# mcu.net
KiCad netlist of a schematic drawn in Altium Designer
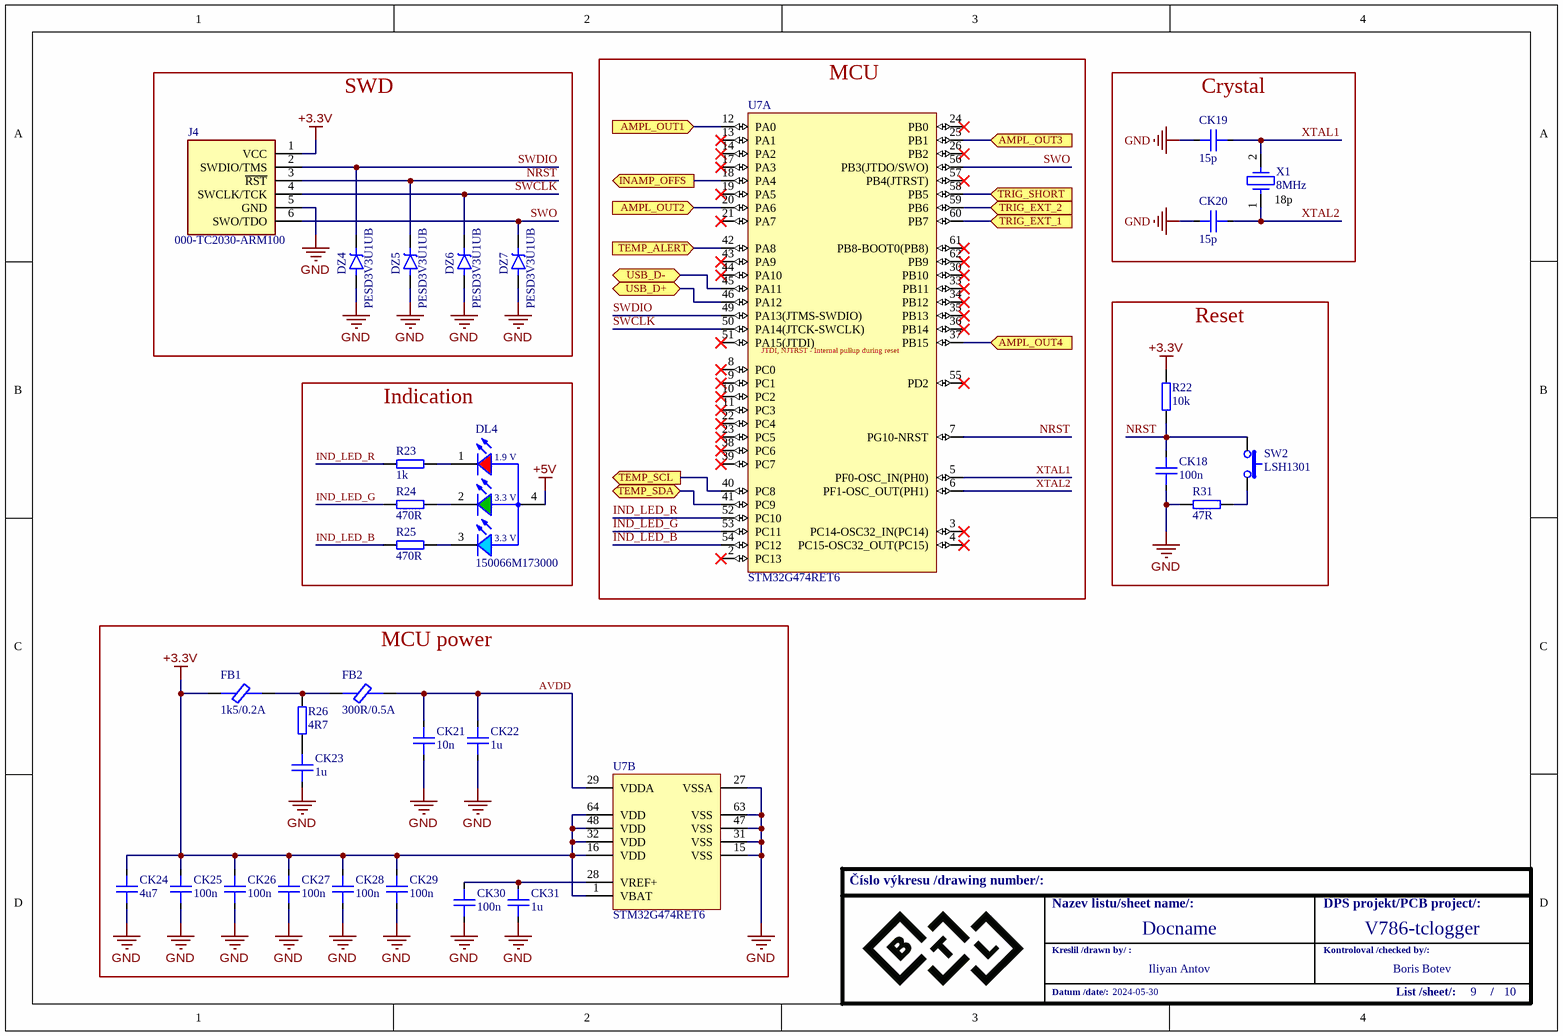
[diagram p0: mcu.SchDoc]

(export (version "E")
  (design (tool "Eeschema 10.0.6"))
  (components
    (comp (ref "CK18")
      (value "100n")
      (footprint "CAPC1608X09N(SMC0603)")
      (description "C; 100n; 100V; 10%; X7R; ??;")
      (fields
        (field (name "MANUFACTURER") "Murata Electronics: GRM188R72A104KA35D;;Yageo: CC0603KRX7R0BB104")
      )
      (libsource (lib "altium_sql") (part "CK"))
    )
    (comp (ref "CK19")
      (value "15p")
      (footprint "CAPC1608X09N(SMC0603)")
      (description "C; 15p; 25V; 5%; NP0/C0G; ??;")
      (fields (field (name "MANUFACTURER") "Samsung: CL10C150JB81PNC"))
      (libsource (lib "altium_sql") (part "CK"))
    )
    (comp (ref "CK20")
      (value "15p")
      (footprint "CAPC1608X09N(SMC0603)")
      (description "C; 15p; 25V; 5%; NP0/C0G; ??;")
      (fields (field (name "MANUFACTURER") "Samsung: CL10C150JB81PNC"))
      (libsource (lib "altium_sql") (part "CK"))
    )
    (comp (ref "CK21")
      (value "10n")
      (footprint "CAPC1608X09N(SMC0603)")
      (description "C; 10n; 50V; 5%; NP0/C0G; ??;")
      (fields (field (name "MANUFACTURER") "TDK: C1608C0G1H103J080AA"))
      (libsource (lib "altium_sql") (part "CK"))
    )
    (comp (ref "CK22")
      (value "1u")
      (footprint "CAPC1608X09N(SMC0603)")
      (description "C; 1u; 50V; 10%; X5R; ??;")
      (libsource (lib "altium_sql") (part "CK"))
    )
    (comp (ref "CK23")
      (value "1u")
      (footprint "CAPC1608X09N(SMC0603)")
      (description "C; 1u; 50V; 10%; X5R; ??;")
      (libsource (lib "altium_sql") (part "CK"))
    )
    (comp (ref "CK24")
      (value "4u7")
      (footprint "CAPC1608X09N(SMC0603)")
      (description "C; 4u7; 25V; 20%; X5R; ??;")
      (fields (field (name "MANUFACTURER") "TDK Corporation: C1608X5R1E475M080AC"))
      (libsource (lib "altium_sql") (part "CK"))
    )
    (comp (ref "CK25")
      (value "100n")
      (footprint "CAPC1608X09N(SMC0603)")
      (description "C; 100n; 100V; 10%; X7R; ??;")
      (fields
        (field (name "MANUFACTURER") "Murata Electronics: GRM188R72A104KA35D;;Yageo: CC0603KRX7R0BB104")
      )
      (libsource (lib "altium_sql") (part "CK"))
    )
    (comp (ref "CK26")
      (value "100n")
      (footprint "CAPC1608X09N(SMC0603)")
      (description "C; 100n; 100V; 10%; X7R; ??;")
      (fields
        (field (name "MANUFACTURER") "Murata Electronics: GRM188R72A104KA35D;;Yageo: CC0603KRX7R0BB104")
      )
      (libsource (lib "altium_sql") (part "CK"))
    )
    (comp (ref "CK27")
      (value "100n")
      (footprint "CAPC1608X09N(SMC0603)")
      (description "C; 100n; 100V; 10%; X7R; ??;")
      (fields
        (field (name "MANUFACTURER") "Murata Electronics: GRM188R72A104KA35D;;Yageo: CC0603KRX7R0BB104")
      )
      (libsource (lib "altium_sql") (part "CK"))
    )
    (comp (ref "CK28")
      (value "100n")
      (footprint "CAPC1608X09N(SMC0603)")
      (description "C; 100n; 100V; 10%; X7R; ??;")
      (fields
        (field (name "MANUFACTURER") "Murata Electronics: GRM188R72A104KA35D;;Yageo: CC0603KRX7R0BB104")
      )
      (libsource (lib "altium_sql") (part "CK"))
    )
    (comp (ref "CK29")
      (value "100n")
      (footprint "CAPC1608X09N(SMC0603)")
      (description "C; 100n; 100V; 10%; X7R; ??;")
      (fields
        (field (name "MANUFACTURER") "Murata Electronics: GRM188R72A104KA35D;;Yageo: CC0603KRX7R0BB104")
      )
      (libsource (lib "altium_sql") (part "CK"))
    )
    (comp (ref "CK30")
      (value "100n")
      (footprint "CAPC1608X09N(SMC0603)")
      (description "C; 100n; 100V; 10%; X7R; ??;")
      (fields
        (field (name "MANUFACTURER") "Murata Electronics: GRM188R72A104KA35D;;Yageo: CC0603KRX7R0BB104")
      )
      (libsource (lib "altium_sql") (part "CK"))
    )
    (comp (ref "CK31")
      (value "1u")
      (footprint "CAPC1608X09N(SMC0603)")
      (description "C; 1u; 50V; 10%; X5R; ??;")
      (libsource (lib "altium_sql") (part "CK"))
    )
    (comp (ref "DL4")
      (value "150066M173000")
      (footprint "WE_150066M173000")
      (description "Ind; Light; Red/Green/Blue;")
      (fields (field (name "MANUFACTURER") "Würth: 150066M173000"))
      (libsource (lib "altium_sql") (part "EDL+150066M173000X00"))
    )
    (comp (ref "DZ4")
      (value "PESD3V3U1UB")
      (footprint "SODFL160X65-2N(SC79)")
      (description "CP; Voltage [V] - Unidirectional; 4.5; R:Yes; 1x;")
      (fields (field (name "MANUFACTURER") "Nexperia: PESD3V3U1UB,115;;NXP: PESD3V3U1UB,115"))
      (libsource (lib "altium_sql") (part "DTU"))
    )
    (comp (ref "DZ5")
      (value "PESD3V3U1UB")
      (footprint "SODFL160X65-2N(SC79)")
      (description "CP; Voltage [V] - Unidirectional; 4.5; R:Yes; 1x;")
      (fields (field (name "MANUFACTURER") "Nexperia: PESD3V3U1UB,115;;NXP: PESD3V3U1UB,115"))
      (libsource (lib "altium_sql") (part "DTU"))
    )
    (comp (ref "DZ6")
      (value "PESD3V3U1UB")
      (footprint "SODFL160X65-2N(SC79)")
      (description "CP; Voltage [V] - Unidirectional; 4.5; R:Yes; 1x;")
      (fields (field (name "MANUFACTURER") "Nexperia: PESD3V3U1UB,115;;NXP: PESD3V3U1UB,115"))
      (libsource (lib "altium_sql") (part "DTU"))
    )
    (comp (ref "DZ7")
      (value "PESD3V3U1UB")
      (footprint "SODFL160X65-2N(SC79)")
      (description "CP; Voltage [V] - Unidirectional; 4.5; R:Yes; 1x;")
      (fields (field (name "MANUFACTURER") "Nexperia: PESD3V3U1UB,115;;NXP: PESD3V3U1UB,115"))
      (libsource (lib "altium_sql") (part "DTU"))
    )
    (comp (ref "FB1")
      (value "1k5/0.2A")
      (footprint "INDC2012X08N(SML0805)")
      (description "Flt; Chip Bead; 0.7Ohm; 0.2A; ??V; 1x;")
      (libsource (lib "altium_sql") (part "L_FB"))
    )
    (comp (ref "FB2")
      (value "300R/0.5A")
      (footprint "MMZ1608")
      (description "Flt; Chip Bead; 0.25Ohm; 0.5A; ??V; 1x;")
      (fields (field (name "MANUFACTURER") "TDK: MMZ1608B301CTAH0;;TDK: MMZ1608B301CT"))
      (libsource (lib "altium_sql") (part "L_FB"))
    )
    (comp (ref "J4")
      (value "000-TC2030-ARM100")
      (footprint "TC2030-MCP-NL")
      (description "De; Programming connector;")
      (libsource (lib "altium_sql") (part "000-TC2030-ARM100"))
    )
    (comp (ref "R22")
      (value "10k")
      (footprint "RESC2012X06N(SMR0805)")
      (description "R; 10k; 0.125W; 1%; 150V; Thick Film; ±100ppm/K; 1x;")
      (libsource (lib "altium_sql") (part "R"))
    )
    (comp (ref "R23")
      (value "1k")
      (footprint "RESC2012X06N(SMR0805)")
      (description "R; 1k; 0.125W; 1%; 150V; Thick Film; ±100ppm/K; 1x;")
      (libsource (lib "altium_sql") (part "R"))
    )
    (comp (ref "R24")
      (value "470R")
      (footprint "RESC1608X06N(SMR0603)")
      (description "R; 470R; 0.1W; 1%; 75V; Thick Film; ±100ppm/K; 1x;")
      (fields (field (name "MANUFACTURER") "Yageo: RC0603FR-07470RL;;Panasonic: ERJ3EKF4700V"))
      (libsource (lib "altium_sql") (part "R"))
    )
    (comp (ref "R25")
      (value "470R")
      (footprint "RESC1608X06N(SMR0603)")
      (description "R; 470R; 0.1W; 1%; 75V; Thick Film; ±100ppm/K; 1x;")
      (fields (field (name "MANUFACTURER") "Yageo: RC0603FR-07470RL;;Panasonic: ERJ3EKF4700V"))
      (libsource (lib "altium_sql") (part "R"))
    )
    (comp (ref "R26")
      (value "4R7")
      (footprint "RESC2012X06N(SMR0805)")
      (description "R; 4R7; 0.125W; 5%; 150V; Thick Film; ±200ppm/K; 1x;")
      (fields (field (name "MANUFACTURER") "YAGEO: RC0805FR-074R7L;;BC Components: MCU0805-50 1% P5 4R7"))
      (libsource (lib "altium_sql") (part "R"))
    )
    (comp (ref "R31")
      (value "47R")
      (footprint "RESC2012X06N(SMR0805)")
      (description "R; 47R; 0.125W; 1%; 150V; Thick Film; ±100ppm/K; 1x;")
      (libsource (lib "altium_sql") (part "R"))
    )
    (comp (ref "SW2")
      (value "LSH1301")
      (footprint "LSH_SWITCH")
      (description "MSw; SPST; PCB; 1x; DC:12V; DC:0.05A; AC:??V; AC:??A; CV:??V; Push-button;")
      (fields (field (name "MANUFACTURER") "DIPTRONICS: DTSM-62N-V-T/R"))
      (libsource (lib "altium_sql") (part "ESW+LSH1301XX0"))
    )
    (comp (ref "U7")
      (value "STM32G474RET6")
      (footprint "TSQFP50P1200X1200X160-64M")
      (libsource (lib "custom-footprints") (part "STM32G474RET6"))
    )
    (comp (ref "X1")
      (value "8MHz")
      (footprint "TXC_7A")
      (description "Oth; Crystal;")
      (fields (field (name "MANUFACTURER") "Abracon: ABM3-8.000MHZ-D2Y-T"))
      (libsource (lib "altium_sql") (part "XTAL_2PIN_1"))
    )
  )
  (nets
    (net (code "1") (name "+3.3V") (class "Default")
      (node (ref "CK24") (pin "2") (pinfunction "2_2") (pintype "passive"))
      (node (ref "CK25") (pin "2") (pinfunction "2_2") (pintype "passive"))
      (node (ref "CK26") (pin "2") (pinfunction "2_2") (pintype "passive"))
      (node (ref "CK27") (pin "2") (pinfunction "2_2") (pintype "passive"))
      (node (ref "CK28") (pin "2") (pinfunction "2_2") (pintype "passive"))
      (node (ref "CK29") (pin "2") (pinfunction "2_2") (pintype "passive"))
      (node (ref "FB1") (pin "1") (pinfunction "L1A_1") (pintype "passive"))
      (node (ref "J4") (pin "1") (pinfunction "VCC_1") (pintype "power_in"))
      (node (ref "R22") (pin "2") (pinfunction "2_2") (pintype "passive"))
      (node (ref "U7") (pin "1") (pinfunction "VBAT_1") (pintype "power_in"))
      (node (ref "U7") (pin "16") (pinfunction "VDD_16") (pintype "power_in"))
      (node (ref "U7") (pin "32") (pinfunction "VDD_32") (pintype "power_in"))
      (node (ref "U7") (pin "48") (pinfunction "VDD_48") (pintype "power_in"))
      (node (ref "U7") (pin "64") (pinfunction "VDD_64") (pintype "power_in"))
    )
    (net (code "2") (name "+5V") (class "Default")
      (node (ref "DL4") (pin "4") (pinfunction "A_4") (pintype "passive"))
    )
    (net (code "3") (name "/AMPL_OUT1") (class "Default")
      (node (ref "U7") (pin "12") (pinfunction "PA0_12") (pintype "bidirectional"))
    )
    (net (code "4") (name "/AMPL_OUT2") (class "Default")
      (node (ref "U7") (pin "20") (pinfunction "PA6_20") (pintype "bidirectional"))
    )
    (net (code "5") (name "/AMPL_OUT3") (class "Default")
      (node (ref "U7") (pin "25") (pinfunction "PB1_25") (pintype "bidirectional"))
    )
    (net (code "6") (name "/AMPL_OUT4") (class "Default")
      (node (ref "U7") (pin "37") (pinfunction "PB15_37") (pintype "bidirectional"))
    )
    (net (code "7") (name "/AVDD") (class "Default")
      (node (ref "CK21") (pin "2") (pinfunction "2_2") (pintype "passive"))
      (node (ref "CK22") (pin "1") (pinfunction "1_1") (pintype "passive"))
      (node (ref "FB2") (pin "2") (pinfunction "L1B_2") (pintype "passive"))
      (node (ref "U7") (pin "29") (pinfunction "VDDA_29") (pintype "power_in"))
    )
    (net (code "8") (name "/INAMP_OFFS") (class "Default")
      (node (ref "U7") (pin "18") (pinfunction "PA4_18") (pintype "bidirectional"))
    )
    (net (code "9") (name "/IND_LED_B") (class "Default")
      (node (ref "R25") (pin "1") (pinfunction "1_1") (pintype "passive"))
      (node (ref "U7") (pin "54") (pinfunction "PC12_54") (pintype "bidirectional"))
    )
    (net (code "10") (name "/IND_LED_G") (class "Default")
      (node (ref "R24") (pin "1") (pinfunction "1_1") (pintype "passive"))
      (node (ref "U7") (pin "53") (pinfunction "PC11_53") (pintype "bidirectional"))
    )
    (net (code "11") (name "/IND_LED_R") (class "Default")
      (node (ref "R23") (pin "2") (pinfunction "2_2") (pintype "passive"))
      (node (ref "U7") (pin "52") (pinfunction "PC10_52") (pintype "bidirectional"))
    )
    (net (code "12") (name "/NRST") (class "Default")
      (node (ref "CK18") (pin "2") (pinfunction "2_2") (pintype "passive"))
      (node (ref "DZ5") (pin "1") (pinfunction "C_1") (pintype "passive"))
      (node (ref "J4") (pin "3") (pinfunction "~{RST}_3") (pintype "passive"))
      (node (ref "R22") (pin "1") (pinfunction "1_1") (pintype "passive"))
      (node (ref "SW2") (pin "1") (pintype "passive"))
      (node (ref "U7") (pin "7") (pinfunction "PG10-NRST_7") (pintype "bidirectional"))
    )
    (net (code "13") (name "/SWCLK") (class "Default")
      (node (ref "DZ6") (pin "1") (pinfunction "C_1") (pintype "passive"))
      (node (ref "J4") (pin "4") (pinfunction "SWCLK/TCK_4") (pintype "passive"))
      (node (ref "U7") (pin "50") (pinfunction "PA14(JTCK-SWCLK)_50") (pintype "bidirectional"))
    )
    (net (code "14") (name "/SWDIO") (class "Default")
      (node (ref "DZ4") (pin "1") (pinfunction "C_1") (pintype "passive"))
      (node (ref "J4") (pin "2") (pinfunction "SWDIO/TMS_2") (pintype "passive"))
      (node (ref "U7") (pin "49") (pinfunction "PA13(JTMS-SWDIO)_49") (pintype "bidirectional"))
    )
    (net (code "15") (name "/SWO") (class "Default")
      (node (ref "DZ7") (pin "1") (pinfunction "C_1") (pintype "passive"))
      (node (ref "J4") (pin "6") (pinfunction "SWO/TDO_6") (pintype "passive"))
      (node (ref "U7") (pin "56") (pinfunction "PB3(JTDO/SWO)_56") (pintype "bidirectional"))
    )
    (net (code "16") (name "/TEMP_ALERT") (class "Default")
      (node (ref "U7") (pin "42") (pinfunction "PA8_42") (pintype "bidirectional"))
    )
    (net (code "17") (name "/TEMP_SCL") (class "Default")
      (node (ref "U7") (pin "40") (pinfunction "PC8_40") (pintype "bidirectional"))
    )
    (net (code "18") (name "/TEMP_SDA") (class "Default")
      (node (ref "U7") (pin "41") (pinfunction "PC9_41") (pintype "bidirectional"))
    )
    (net (code "19") (name "/TRIG_EXT_1") (class "Default")
      (node (ref "U7") (pin "60") (pinfunction "PB7_60") (pintype "bidirectional"))
    )
    (net (code "20") (name "/TRIG_EXT_2") (class "Default")
      (node (ref "U7") (pin "59") (pinfunction "PB6_59") (pintype "bidirectional"))
    )
    (net (code "21") (name "/TRIG_SHORT") (class "Default")
      (node (ref "U7") (pin "58") (pinfunction "PB5_58") (pintype "bidirectional"))
    )
    (net (code "22") (name "/USB_D+") (class "Default")
      (node (ref "U7") (pin "46") (pinfunction "PA12_46") (pintype "bidirectional"))
    )
    (net (code "23") (name "/USB_D-") (class "Default")
      (node (ref "U7") (pin "45") (pinfunction "PA11_45") (pintype "bidirectional"))
    )
    (net (code "24") (name "/XTAL1") (class "Default")
      (node (ref "CK19") (pin "1") (pinfunction "1_1") (pintype "passive"))
      (node (ref "U7") (pin "5") (pinfunction "PF0-OSC_IN(PH0)_5") (pintype "bidirectional"))
      (node (ref "X1") (pin "2") (pintype "passive"))
    )
    (net (code "25") (name "/XTAL2") (class "Default")
      (node (ref "CK20") (pin "1") (pinfunction "1_1") (pintype "passive"))
      (node (ref "U7") (pin "6") (pinfunction "PF1-OSC_OUT(PH1)_6") (pintype "bidirectional"))
      (node (ref "X1") (pin "1") (pintype "passive"))
    )
    (net (code "26") (name "GND") (class "Default")
      (node (ref "CK18") (pin "1") (pinfunction "1_1") (pintype "passive"))
      (node (ref "CK19") (pin "2") (pinfunction "2_2") (pintype "passive"))
      (node (ref "CK20") (pin "2") (pinfunction "2_2") (pintype "passive"))
      (node (ref "CK21") (pin "1") (pinfunction "1_1") (pintype "passive"))
      (node (ref "CK22") (pin "2") (pinfunction "2_2") (pintype "passive"))
      (node (ref "CK23") (pin "2") (pinfunction "2_2") (pintype "passive"))
      (node (ref "CK24") (pin "1") (pinfunction "1_1") (pintype "passive"))
      (node (ref "CK25") (pin "1") (pinfunction "1_1") (pintype "passive"))
      (node (ref "CK26") (pin "1") (pinfunction "1_1") (pintype "passive"))
      (node (ref "CK27") (pin "1") (pinfunction "1_1") (pintype "passive"))
      (node (ref "CK28") (pin "1") (pinfunction "1_1") (pintype "passive"))
      (node (ref "CK29") (pin "1") (pinfunction "1_1") (pintype "passive"))
      (node (ref "CK30") (pin "1") (pinfunction "1_1") (pintype "passive"))
      (node (ref "CK31") (pin "2") (pinfunction "2_2") (pintype "passive"))
      (node (ref "DZ4") (pin "2") (pinfunction "A_2") (pintype "passive"))
      (node (ref "DZ5") (pin "2") (pinfunction "A_2") (pintype "passive"))
      (node (ref "DZ6") (pin "2") (pinfunction "A_2") (pintype "passive"))
      (node (ref "DZ7") (pin "2") (pinfunction "A_2") (pintype "passive"))
      (node (ref "J4") (pin "5") (pinfunction "GND_5") (pintype "power_in"))
      (node (ref "R31") (pin "2") (pinfunction "2_2") (pintype "passive"))
      (node (ref "U7") (pin "15") (pinfunction "VSS_15") (pintype "power_in"))
      (node (ref "U7") (pin "27") (pinfunction "VSSA_27") (pintype "power_in"))
      (node (ref "U7") (pin "31") (pinfunction "VSS_31") (pintype "power_in"))
      (node (ref "U7") (pin "47") (pinfunction "VSS_47") (pintype "power_in"))
      (node (ref "U7") (pin "63") (pinfunction "VSS_63") (pintype "power_in"))
    )
    (net (code "27") (name "Net-(CK23-Pad1)") (class "Default")
      (node (ref "CK23") (pin "1") (pinfunction "1_1") (pintype "passive"))
      (node (ref "R26") (pin "1") (pinfunction "1_1") (pintype "passive"))
    )
    (net (code "28") (name "Net-(DL4-K-Pad1)") (class "Default")
      (node (ref "DL4") (pin "1") (pinfunction "K_1") (pintype "passive"))
      (node (ref "R23") (pin "1") (pinfunction "1_1") (pintype "passive"))
    )
    (net (code "29") (name "Net-(DL4-K-Pad2)") (class "Default")
      (node (ref "DL4") (pin "2") (pinfunction "K_2") (pintype "passive"))
      (node (ref "R24") (pin "2") (pinfunction "2_2") (pintype "passive"))
    )
    (net (code "30") (name "Net-(DL4-K-Pad3)") (class "Default")
      (node (ref "DL4") (pin "3") (pinfunction "K_3") (pintype "passive"))
      (node (ref "R25") (pin "2") (pinfunction "2_2") (pintype "passive"))
    )
    (net (code "31") (name "Net-(FB1-L1B)") (class "Default")
      (node (ref "FB1") (pin "2") (pinfunction "L1B_2") (pintype "passive"))
      (node (ref "FB2") (pin "1") (pinfunction "L1A_1") (pintype "passive"))
      (node (ref "R26") (pin "2") (pinfunction "2_2") (pintype "passive"))
    )
    (net (code "32") (name "Net-(R31-Pad1)") (class "Default")
      (node (ref "R31") (pin "1") (pinfunction "1_1") (pintype "passive"))
      (node (ref "SW2") (pin "3") (pintype "passive"))
    )
    (net (code "33") (name "Net-(U7B-VREF+)") (class "Default")
      (node (ref "CK30") (pin "2") (pinfunction "2_2") (pintype "passive"))
      (node (ref "CK31") (pin "1") (pinfunction "1_1") (pintype "passive"))
      (node (ref "U7") (pin "28") (pinfunction "VREF+_28") (pintype "power_in"))
    )
    (net (code "34") (name "unconnected-(U7A-PA1-Pad13)") (class "Default")
      (node (ref "U7") (pin "13") (pinfunction "PA1_13") (pintype "bidirectional+no_connect"))
    )
    (net (code "35") (name "unconnected-(U7A-PA2-Pad14)") (class "Default")
      (node (ref "U7") (pin "14") (pinfunction "PA2_14") (pintype "bidirectional+no_connect"))
    )
    (net (code "36") (name "unconnected-(U7A-PA3-Pad17)") (class "Default")
      (node (ref "U7") (pin "17") (pinfunction "PA3_17") (pintype "bidirectional+no_connect"))
    )
    (net (code "37") (name "unconnected-(U7A-PA5-Pad19)") (class "Default")
      (node (ref "U7") (pin "19") (pinfunction "PA5_19") (pintype "bidirectional+no_connect"))
    )
    (net (code "38") (name "unconnected-(U7A-PA7-Pad21)") (class "Default")
      (node (ref "U7") (pin "21") (pinfunction "PA7_21") (pintype "bidirectional+no_connect"))
    )
    (net (code "39") (name "unconnected-(U7A-PA9-Pad43)") (class "Default")
      (node (ref "U7") (pin "43") (pinfunction "PA9_43") (pintype "bidirectional+no_connect"))
    )
    (net (code "40") (name "unconnected-(U7A-PA10-Pad44)") (class "Default")
      (node (ref "U7") (pin "44") (pinfunction "PA10_44") (pintype "bidirectional+no_connect"))
    )
    (net (code "41") (name "unconnected-(U7A-PA15(JTDI)-Pad51)") (class "Default")
      (node (ref "U7") (pin "51") (pinfunction "PA15(JTDI)_51") (pintype "bidirectional+no_connect"))
    )
    (net (code "42") (name "unconnected-(U7A-PB0-Pad24)") (class "Default")
      (node (ref "U7") (pin "24") (pinfunction "PB0_24") (pintype "bidirectional+no_connect"))
    )
    (net (code "43") (name "unconnected-(U7A-PB2-Pad26)") (class "Default")
      (node (ref "U7") (pin "26") (pinfunction "PB2_26") (pintype "bidirectional+no_connect"))
    )
    (net (code "44") (name "unconnected-(U7A-PB4(JTRST)-Pad57)") (class "Default")
      (node (ref "U7") (pin "57") (pinfunction "PB4(JTRST)_57") (pintype "bidirectional+no_connect"))
    )
    (net (code "45") (name "unconnected-(U7A-PB8-BOOT0(PB8)-Pad61)") (class "Default")
      (node (ref "U7") (pin "61") (pinfunction "PB8-BOOT0(PB8)_61") (pintype "bidirectional+no_connect"))
    )
    (net (code "46") (name "unconnected-(U7A-PB9-Pad62)") (class "Default")
      (node (ref "U7") (pin "62") (pinfunction "PB9_62") (pintype "bidirectional+no_connect"))
    )
    (net (code "47") (name "unconnected-(U7A-PB10-Pad30)") (class "Default")
      (node (ref "U7") (pin "30") (pinfunction "PB10_30") (pintype "bidirectional+no_connect"))
    )
    (net (code "48") (name "unconnected-(U7A-PB11-Pad33)") (class "Default")
      (node (ref "U7") (pin "33") (pinfunction "PB11_33") (pintype "bidirectional+no_connect"))
    )
    (net (code "49") (name "unconnected-(U7A-PB12-Pad34)") (class "Default")
      (node (ref "U7") (pin "34") (pinfunction "PB12_34") (pintype "bidirectional+no_connect"))
    )
    (net (code "50") (name "unconnected-(U7A-PB13-Pad35)") (class "Default")
      (node (ref "U7") (pin "35") (pinfunction "PB13_35") (pintype "bidirectional+no_connect"))
    )
    (net (code "51") (name "unconnected-(U7A-PB14-Pad36)") (class "Default")
      (node (ref "U7") (pin "36") (pinfunction "PB14_36") (pintype "bidirectional+no_connect"))
    )
    (net (code "52") (name "unconnected-(U7A-PC0-Pad8)") (class "Default")
      (node (ref "U7") (pin "8") (pinfunction "PC0_8") (pintype "bidirectional+no_connect"))
    )
    (net (code "53") (name "unconnected-(U7A-PC1-Pad9)") (class "Default")
      (node (ref "U7") (pin "9") (pinfunction "PC1_9") (pintype "bidirectional+no_connect"))
    )
    (net (code "54") (name "unconnected-(U7A-PC2-Pad10)") (class "Default")
      (node (ref "U7") (pin "10") (pinfunction "PC2_10") (pintype "bidirectional+no_connect"))
    )
    (net (code "55") (name "unconnected-(U7A-PC3-Pad11)") (class "Default")
      (node (ref "U7") (pin "11") (pinfunction "PC3_11") (pintype "bidirectional+no_connect"))
    )
    (net (code "56") (name "unconnected-(U7A-PC4-Pad22)") (class "Default")
      (node (ref "U7") (pin "22") (pinfunction "PC4_22") (pintype "bidirectional+no_connect"))
    )
    (net (code "57") (name "unconnected-(U7A-PC5-Pad23)") (class "Default")
      (node (ref "U7") (pin "23") (pinfunction "PC5_23") (pintype "bidirectional+no_connect"))
    )
    (net (code "58") (name "unconnected-(U7A-PC6-Pad38)") (class "Default")
      (node (ref "U7") (pin "38") (pinfunction "PC6_38") (pintype "bidirectional+no_connect"))
    )
    (net (code "59") (name "unconnected-(U7A-PC7-Pad39)") (class "Default")
      (node (ref "U7") (pin "39") (pinfunction "PC7_39") (pintype "bidirectional+no_connect"))
    )
    (net (code "60") (name "unconnected-(U7A-PC13-Pad2)") (class "Default")
      (node (ref "U7") (pin "2") (pinfunction "PC13_2") (pintype "bidirectional+no_connect"))
    )
    (net (code "61") (name "unconnected-(U7A-PC14-OSC32_IN(PC14)-Pad3)") (class "Default")
      (node (ref "U7") (pin "3") (pinfunction "PC14-OSC32_IN(PC14)_3") (pintype "bidirectional+no_connect"))
    )
    (net (code "62") (name "unconnected-(U7A-PC15-OSC32_OUT(PC15)-Pad4)") (class "Default")
      (node (ref "U7") (pin "4") (pinfunction "PC15-OSC32_OUT(PC15)_4") (pintype "bidirectional+no_connect"))
    )
    (net (code "63") (name "unconnected-(U7A-PD2-Pad55)") (class "Default")
      (node (ref "U7") (pin "55") (pinfunction "PD2_55") (pintype "bidirectional+no_connect"))
    )
  )
)
